# GrainDryer.net
KiCad netlist of a schematic drawn in Altium Designer
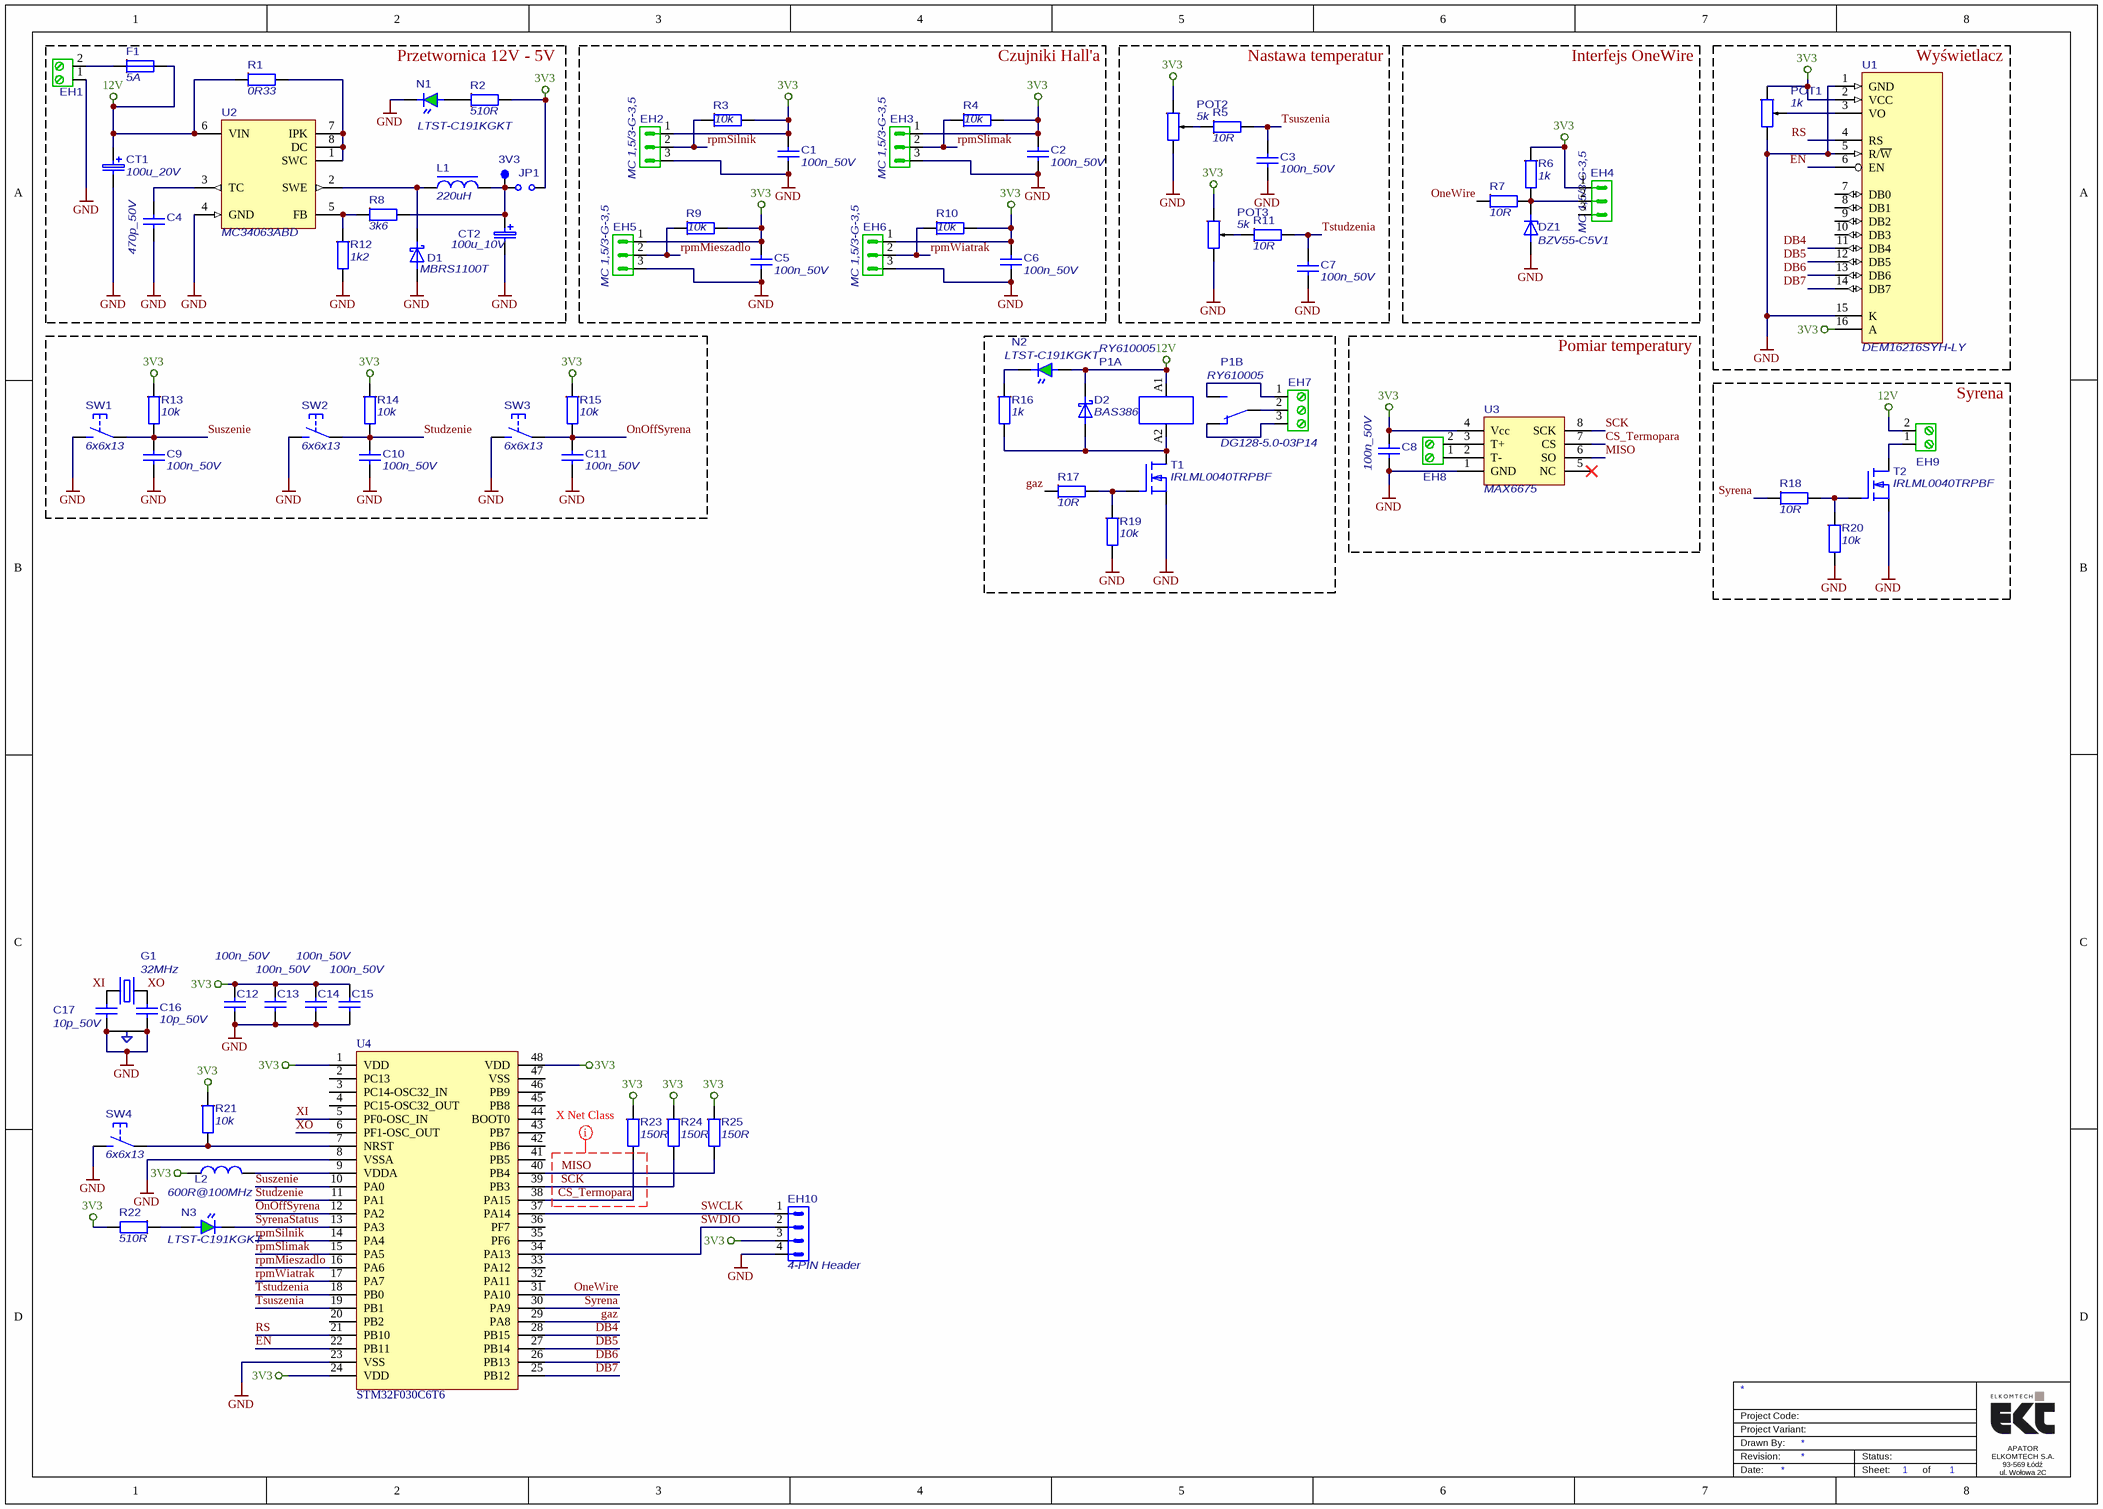
[diagram p0: GrainDryer.SchDoc]

(export (version "E")
  (design (tool "Eeschema 10.0.6"))
  (components
    (comp (ref "3V3")
      (value "TP_THT")
      (footprint "TP3")
      (description "Test Point, THT")
      (libsource (lib "manufacturing") (part "TP THT Dia{colon} 0,7mm"))
    )
    (comp (ref "C1")
      (value "100n_50V")
      (footprint "0603C")
      (description "Capacitor")
      (fields (field (name "TOLERANCE") "10") (field (name "MANUFACTURER") "MULTICOMP"))
      (libsource (lib "capacitor_smd") (part "100n 10% 50V 0603 [Metric{colon} 1608] X7R"))
    )
    (comp (ref "C2")
      (value "100n_50V")
      (footprint "0603C")
      (description "Capacitor")
      (fields (field (name "TOLERANCE") "10") (field (name "MANUFACTURER") "MULTICOMP"))
      (libsource (lib "capacitor_smd") (part "100n 10% 50V 0603 [Metric{colon} 1608] X7R"))
    )
    (comp (ref "C3")
      (value "100n_50V")
      (footprint "0603C")
      (description "Capacitor")
      (fields (field (name "TOLERANCE") "10") (field (name "MANUFACTURER") "MULTICOMP"))
      (libsource (lib "capacitor_smd") (part "100n 10% 50V 0603 [Metric{colon} 1608] X7R"))
    )
    (comp (ref "C4")
      (value "470p_50V")
      (footprint "1206C")
      (description "Capacitor")
      (fields (field (name "TOLERANCE") "5") (field (name "MANUFACTURER") "KEMET"))
      (libsource (lib "capacitor_smd") (part "470p 5% 50V 1206 [Metric{colon} 3216]"))
    )
    (comp (ref "C5")
      (value "100n_50V")
      (footprint "0603C")
      (description "Capacitor")
      (fields (field (name "TOLERANCE") "10") (field (name "MANUFACTURER") "MULTICOMP"))
      (libsource (lib "capacitor_smd") (part "100n 10% 50V 0603 [Metric{colon} 1608] X7R"))
    )
    (comp (ref "C6")
      (value "100n_50V")
      (footprint "0603C")
      (description "Capacitor")
      (fields (field (name "TOLERANCE") "10") (field (name "MANUFACTURER") "MULTICOMP"))
      (libsource (lib "capacitor_smd") (part "100n 10% 50V 0603 [Metric{colon} 1608] X7R"))
    )
    (comp (ref "C7")
      (value "100n_50V")
      (footprint "0603C")
      (description "Capacitor")
      (fields (field (name "TOLERANCE") "10") (field (name "MANUFACTURER") "MULTICOMP"))
      (libsource (lib "capacitor_smd") (part "100n 10% 50V 0603 [Metric{colon} 1608] X7R"))
    )
    (comp (ref "C8")
      (value "100n_50V")
      (footprint "0603C")
      (description "Capacitor")
      (fields (field (name "TOLERANCE") "10") (field (name "MANUFACTURER") "MULTICOMP"))
      (libsource (lib "capacitor_smd") (part "100n 10% 50V 0603 [Metric{colon} 1608] X7R"))
    )
    (comp (ref "C9")
      (value "100n_50V")
      (footprint "0603C")
      (description "Capacitor")
      (fields (field (name "TOLERANCE") "10") (field (name "MANUFACTURER") "MULTICOMP"))
      (libsource (lib "capacitor_smd") (part "100n 10% 50V 0603 [Metric{colon} 1608] X7R"))
    )
    (comp (ref "C10")
      (value "100n_50V")
      (footprint "0603C")
      (description "Capacitor")
      (fields (field (name "TOLERANCE") "10") (field (name "MANUFACTURER") "MULTICOMP"))
      (libsource (lib "capacitor_smd") (part "100n 10% 50V 0603 [Metric{colon} 1608] X7R"))
    )
    (comp (ref "C11")
      (value "100n_50V")
      (footprint "0603C")
      (description "Capacitor")
      (fields (field (name "TOLERANCE") "10") (field (name "MANUFACTURER") "MULTICOMP"))
      (libsource (lib "capacitor_smd") (part "100n 10% 50V 0603 [Metric{colon} 1608] X7R"))
    )
    (comp (ref "C12")
      (value "100n_50V")
      (footprint "0603C")
      (description "Capacitor")
      (fields (field (name "TOLERANCE") "10") (field (name "MANUFACTURER") "MULTICOMP"))
      (libsource (lib "capacitor_smd") (part "100n 10% 50V 0603 [Metric{colon} 1608] X7R"))
    )
    (comp (ref "C13")
      (value "100n_50V")
      (footprint "0603C")
      (description "Capacitor")
      (fields (field (name "TOLERANCE") "10") (field (name "MANUFACTURER") "MULTICOMP"))
      (libsource (lib "capacitor_smd") (part "100n 10% 50V 0603 [Metric{colon} 1608] X7R"))
    )
    (comp (ref "C14")
      (value "100n_50V")
      (footprint "0603C")
      (description "Capacitor")
      (fields (field (name "TOLERANCE") "10") (field (name "MANUFACTURER") "MULTICOMP"))
      (libsource (lib "capacitor_smd") (part "100n 10% 50V 0603 [Metric{colon} 1608] X7R"))
    )
    (comp (ref "C15")
      (value "100n_50V")
      (footprint "0603C")
      (description "Capacitor")
      (fields (field (name "TOLERANCE") "10") (field (name "MANUFACTURER") "MULTICOMP"))
      (libsource (lib "capacitor_smd") (part "100n 10% 50V 0603 [Metric{colon} 1608] X7R"))
    )
    (comp (ref "C16")
      (value "10p_50V")
      (footprint "0603H")
      (description "Capacitor")
      (fields (field (name "TOLERANCE") "5") (field (name "MANUFACTURER") "KEMET"))
      (libsource (lib "capacitor_smd") (part "10p 5% 50V 0603 [Metric{colon} 1608] C0G"))
    )
    (comp (ref "C17")
      (value "10p_50V")
      (footprint "0603H")
      (description "Capacitor")
      (fields (field (name "TOLERANCE") "5") (field (name "MANUFACTURER") "KEMET"))
      (libsource (lib "capacitor_smd") (part "10p 5% 50V 0603 [Metric{colon} 1608] C0G"))
    )
    (comp (ref "CT1")
      (value "100u_20V")
      (footprint "7243")
      (description "Tantalum Capacitor")
      (fields
        (field (name "MANUFACTURER") "AVX")
        (field (name "MANUFACTURER PART NUMBER") "TPSD107K020R0085")
      )
      (libsource (lib "capacitor_polarized_smd") (part "100u 10% 20V 2917 [Metric{colon} 7343] 0R085"))
    )
    (comp (ref "CT2")
      (value "100u_10V")
      (footprint "7243")
      (description "Tantalum Capacitor")
      (fields
        (field (name "MANUFACTURER") "AVX")
        (field (name "MANUFACTURER PART NUMBER") "TPSD107K010R0065")
      )
      (libsource (lib "capacitor_polarized_smd") (part "100u 10% 10V 2917 [Metric{colon} 7343] 0R065"))
    )
    (comp (ref "D1")
      (value "MBRS1100T")
      (footprint "CASE403A-03")
      (description "Schottky Diodes & Rectifiers")
      (fields
        (field (name "MANUFACTURER") "ON SEMICONDUCTOR")
        (field (name "MANUFACTURER PART NUMBER") "MBRS1100T3G")
      )
      (libsource (lib "diode_smd") (part "MBRS1100T3G 100V 1A SMB"))
    )
    (comp (ref "D2")
      (value "BAS386")
      (footprint "MICROMELF")
      (description "Schottky Diode")
      (fields (field (name "MANUFACTURER") "VISHAY") (field (name "MANUFACTURER PART NUMBER") "BAS386-TR"))
      (libsource (lib "diode_smd") (part "BAS386-TR 50V 0,1A Micro MELF"))
    )
    (comp (ref "DZ1")
      (value "BZV55-C5V1")
      (footprint "SOD80D")
      (description "Zener Diodes")
      (fields (field (name "MANUFACTURER") "NXP") (field (name "POWER") "0,5"))
      (libsource (lib "diode_zener_smd") (part "BZV55-C5V1 5,1V 2uA 500mW SOD-80"))
    )
    (comp (ref "EH1")
      (value "MKDSN 1,5/2-5,08")
      (footprint "2xMKDSN1.5")
      (description "Term. block 13,5A 250V")
      (fields
        (field (name "MANUFACTURER") "PHOENIX CONTACT")
        (field (name "MANUFACTURER PART NUMBER") "1729128")
      )
      (libsource (lib "phoenix_contact") (part "MKDSN 1,5/2-5,08 1729128"))
    )
    (comp (ref "EH2")
      (value "MC 1,5/3-G-3,5")
      (footprint "MC 1,5/3-G-3,5")
      (description "Header 8A 250V")
      (fields
        (field (name "MANUFACTURER") "PHOENIX CONTACT")
        (field (name "MANUFACTURER PART NUMBER") "1844223")
      )
      (libsource (lib "phoenix_contact") (part "MC 1,5/3-G-3,5 1844223"))
    )
    (comp (ref "EH3")
      (value "MC 1,5/3-G-3,5")
      (footprint "MC 1,5/3-G-3,5")
      (description "Header 8A 250V")
      (fields
        (field (name "MANUFACTURER") "PHOENIX CONTACT")
        (field (name "MANUFACTURER PART NUMBER") "1844223")
      )
      (libsource (lib "phoenix_contact") (part "MC 1,5/3-G-3,5 1844223"))
    )
    (comp (ref "EH4")
      (value "MC 1,5/3-G-3,5")
      (footprint "MC 1,5/3-G-3,5")
      (description "Header 8A 250V")
      (fields
        (field (name "MANUFACTURER") "PHOENIX CONTACT")
        (field (name "MANUFACTURER PART NUMBER") "1844223")
      )
      (libsource (lib "") (part "MC 1,5/3-G-3,5 1844223_1"))
    )
    (comp (ref "EH5")
      (value "MC 1,5/3-G-3,5")
      (footprint "MC 1,5/3-G-3,5")
      (description "Header 8A 250V")
      (fields
        (field (name "MANUFACTURER") "PHOENIX CONTACT")
        (field (name "MANUFACTURER PART NUMBER") "1844223")
      )
      (libsource (lib "phoenix_contact") (part "MC 1,5/3-G-3,5 1844223"))
    )
    (comp (ref "EH6")
      (value "MC 1,5/3-G-3,5")
      (footprint "MC 1,5/3-G-3,5")
      (description "Header 8A 250V")
      (fields
        (field (name "MANUFACTURER") "PHOENIX CONTACT")
        (field (name "MANUFACTURER PART NUMBER") "1844223")
      )
      (libsource (lib "phoenix_contact") (part "MC 1,5/3-G-3,5 1844223"))
    )
    (comp (ref "EH7")
      (value "DG128-5.0-03P14")
      (footprint "DG128-5.0-03P14")
      (description "Term. block 5mm")
      (fields
        (field (name "MANUFACTURER") "DEGSON ELECTRONICS")
        (field (name "MANUFACTURER PART NUMBER") "DG128-5.0-03P-14-00A(H)")
      )
      (libsource (lib "connector_pcb") (part "DG128-5.0-03P14"))
    )
    (comp (ref "EH8")
      (value "MKDSN 1,5/2-5,08")
      (footprint "2xMKDSN1.5")
      (description "Term. block 13,5A 250V")
      (fields
        (field (name "MANUFACTURER") "PHOENIX CONTACT")
        (field (name "MANUFACTURER PART NUMBER") "1729128")
      )
      (libsource (lib "phoenix_contact") (part "MKDSN 1,5/2-5,08 1729128"))
    )
    (comp (ref "EH9")
      (value "MKDSN 1,5/2-5,08")
      (footprint "2xMKDSN1.5")
      (description "Term. block 13,5A 250V")
      (fields
        (field (name "MANUFACTURER") "PHOENIX CONTACT")
        (field (name "MANUFACTURER PART NUMBER") "1729128")
      )
      (libsource (lib "") (part "MKDSN 1,5/2-5,08 1729128_1"))
    )
    (comp (ref "EH10")
      (value "4-PIN Header")
      (footprint "SIP4")
      (description "1x4, Male, Pitch 2,54mm")
      (fields
        (field (name "MANUFACTURER") "CONNFLY")
        (field (name "MANUFACTURER PART NUMBER") "DS1021-1*4SF1-1")
      )
      (libsource (lib "connector_pcb") (part "4-PIN Header 2,54 DS1021-1*4SF1-1"))
    )
    (comp (ref "F1")
      (value "5A")
      (footprint "20x5mm fuse holder")
      (description "Fuse")
      (fields (field (name "MANUFACTURER") "multicom") (field (name "MANUFACTURER PART NUMBER") "MC000827"))
      (libsource (lib "protection") (part "5A fuse 20x5mm"))
    )
    (comp (ref "G1")
      (value "32MHz")
      (footprint "XTAL2520")
      (description "25MHz; ±30ppm; 20pF; SMD; 2,6x2,1x0,65mm")
      (fields (field (name "MANUFACTURER") "YIC") (field (name "MANUFACTURER PART NUMBER") "32.00M-SMDXT224"))
      (libsource (lib "crystal_oscillator") (part "32.00M-SMDXT224 25MHz 30ppm -V 2,6x2,1"))
    )
    (comp (ref "JP1")
      (value "JP_2H_NO")
      (footprint "TIN2")
      (description "Jumper 2-contact, normally open")
      (libsource (lib "jumper") (part "JP 2H NO"))
    )
    (comp (ref "L1")
      (value "220uH")
      (footprint "SRR0604")
      (description "Power shielded 1R7")
      (fields
        (field (name "MANUFACTURER") "BOURNS")
        (field (name "MANUFACTURER PART NUMBER") "SRR0604-221KL")
      )
      (libsource (lib "inductor_smd") (part "220uH 0,25A 6,5x6,5x4,8"))
    )
    (comp (ref "L2")
      (value "600R@100MHz")
      (footprint "1206L")
      (description "EMI")
      (fields
        (field (name "MANUFACTURER") "MURATA")
        (field (name "MANUFACTURER PART NUMBER") "BLM31PG601SN1")
      )
      (libsource (lib "inductor_smd") (part "600R@100MHz 1,5A 1206"))
    )
    (comp (ref "N1")
      (value "LTST-C191KGKT")
      (footprint "LED0603GREEN")
      (description "LED SMD 12mcd")
      (fields (field (name "MANUFACTURER") "LITE-ON"))
      (libsource (lib "diode_led_smd") (part "LTST-C191KGKT Green 0603 [Metric{colon} 1608]"))
    )
    (comp (ref "N2")
      (value "LTST-C191KGKT")
      (footprint "LED0603GREEN")
      (description "LED SMD 12mcd")
      (fields (field (name "MANUFACTURER") "LITE-ON"))
      (libsource (lib "diode_led_smd") (part "LTST-C191KGKT Green 0603 [Metric{colon} 1608]"))
    )
    (comp (ref "N3")
      (value "LTST-C191KGKT")
      (footprint "LED0603GREEN")
      (description "LED SMD 12mcd")
      (fields (field (name "MANUFACTURER") "LITE-ON"))
      (libsource (lib "diode_led_smd") (part "LTST-C191KGKT Green 0603 [Metric{colon} 1608]"))
    )
    (comp (ref "P1")
      (value "RY610005")
      (footprint "RY6100XX")
      (description "General Purpose Relays SPDT 8 A 5VDC")
      (fields (field (name "MANUFACTURER") "SCHRACK"))
      (libsource (lib "") (part "RY610005_1"))
    )
    (comp (ref "POT1")
      (value "1k")
      (footprint "3312J")
      (description "Potentiometer")
      (fields (field (name "MANUFACTURER") "BOURNS") (field (name "MANUFACTURER PART NUMBER") "3312J-1-102E"))
      (libsource (lib "potentiometers") (part "1k 20% 0,1W SMD"))
    )
    (comp (ref "POT2")
      (value "5k")
      (footprint "3d_pot:RK09 vertical")
      (description "Potentiometer")
      (fields
        (field (name "MANUFACTURER") "SR PASSIVES")
        (field (name "MANUFACTURER PART NUMBER") "R9011-1-5K")
      )
      (libsource (lib "potentiometers") (part "5k 20% 1/8W THT RK09"))
    )
    (comp (ref "POT3")
      (value "5k")
      (footprint "3d_pot:RK09 vertical")
      (description "Potentiometer")
      (fields
        (field (name "MANUFACTURER") "SR PASSIVES")
        (field (name "MANUFACTURER PART NUMBER") "R9011-1-5K")
      )
      (libsource (lib "potentiometers") (part "5k 20% 1/8W THT RK09"))
    )
    (comp (ref "R1")
      (value "0R33")
      (footprint "2512R")
      (description "Resistor")
      (fields
        (field (name "MANUFACTURER") "YAGEO")
        (field (name "MANUFACTURER PART NUMBER") "RL2512JK-070R02L")
      )
      (libsource (lib "resistor_smd") (part "0R33 5% 1W 2512 [Metric{colon} 6432]"))
    )
    (comp (ref "R2")
      (value "510R")
      (footprint "0603R")
      (description "Resistor")
      (fields
        (field (name "MANUFACTURER") "YAGEO")
        (field (name "MANUFACTURER PART NUMBER") "RC0603JR-07510RL")
      )
      (libsource (lib "") (part "510R 5% 0,1W 0603 [Metric{colon} 1608]_1"))
    )
    (comp (ref "R3")
      (value "10k")
      (footprint "0603R")
      (description "Resistor")
      (fields
        (field (name "MANUFACTURER") "YAGEO")
        (field (name "MANUFACTURER PART NUMBER") "RC0603JR-0710KL")
      )
      (libsource (lib "resistor_smd") (part "10k 5% 0,1W 0603 [Metric{colon} 1608]"))
    )
    (comp (ref "R4")
      (value "10k")
      (footprint "0603R")
      (description "Resistor")
      (fields
        (field (name "MANUFACTURER") "YAGEO")
        (field (name "MANUFACTURER PART NUMBER") "RC0603JR-0710KL")
      )
      (libsource (lib "resistor_smd") (part "10k 5% 0,1W 0603 [Metric{colon} 1608]"))
    )
    (comp (ref "R5")
      (value "10R")
      (footprint "0603R")
      (description "Resistor")
      (fields
        (field (name "MANUFACTURER") "PANASONIC")
        (field (name "MANUFACTURER PART NUMBER") "ERJ3EKF10R0V")
      )
      (libsource (lib "resistor_smd") (part "10R 1% 0,1W 0603 [Metric{colon} 1608]"))
    )
    (comp (ref "R6")
      (value "1k")
      (footprint "0603R")
      (description "Resistor")
      (fields
        (field (name "MANUFACTURER") "YAGEO")
        (field (name "MANUFACTURER PART NUMBER") "RC0603JR-071KL")
      )
      (libsource (lib "") (part "1k 5% 0,1W 0603 [Metric{colon} 1608]_1"))
    )
    (comp (ref "R7")
      (value "10R")
      (footprint "0603R")
      (description "Resistor")
      (fields
        (field (name "MANUFACTURER") "PANASONIC")
        (field (name "MANUFACTURER PART NUMBER") "ERJ3EKF10R0V")
      )
      (libsource (lib "resistor_smd") (part "10R 1% 0,1W 0603 [Metric{colon} 1608]"))
    )
    (comp (ref "R8")
      (value "3k6")
      (footprint "1206R")
      (description "Resistor")
      (fields
        (field (name "MANUFACTURER") "PANASONIC")
        (field (name "MANUFACTURER PART NUMBER") "ERJ8ENF3601V")
      )
      (libsource (lib "resistor_smd") (part "3k6 1% 0,25W 1206 [Metric{colon} 3216]"))
    )
    (comp (ref "R9")
      (value "10k")
      (footprint "0603R")
      (description "Resistor")
      (fields
        (field (name "MANUFACTURER") "YAGEO")
        (field (name "MANUFACTURER PART NUMBER") "RC0603JR-0710KL")
      )
      (libsource (lib "resistor_smd") (part "10k 5% 0,1W 0603 [Metric{colon} 1608]"))
    )
    (comp (ref "R10")
      (value "10k")
      (footprint "0603R")
      (description "Resistor")
      (fields
        (field (name "MANUFACTURER") "YAGEO")
        (field (name "MANUFACTURER PART NUMBER") "RC0603JR-0710KL")
      )
      (libsource (lib "resistor_smd") (part "10k 5% 0,1W 0603 [Metric{colon} 1608]"))
    )
    (comp (ref "R11")
      (value "10R")
      (footprint "0603R")
      (description "Resistor")
      (fields
        (field (name "MANUFACTURER") "PANASONIC")
        (field (name "MANUFACTURER PART NUMBER") "ERJ3EKF10R0V")
      )
      (libsource (lib "resistor_smd") (part "10R 1% 0,1W 0603 [Metric{colon} 1608]"))
    )
    (comp (ref "R12")
      (value "1k2")
      (footprint "1206R")
      (description "Resistor")
      (fields
        (field (name "MANUFACTURER") "ROYAL OHM")
        (field (name "MANUFACTURER PART NUMBER") "1206S4F0122T5E")
      )
      (libsource (lib "resistor_smd") (part "1k2 1% 0,25W 1206 [Metric{colon} 3216]"))
    )
    (comp (ref "R13")
      (value "10k")
      (footprint "0603R")
      (description "Resistor")
      (fields
        (field (name "MANUFACTURER") "YAGEO")
        (field (name "MANUFACTURER PART NUMBER") "RC0603JR-0710KL")
      )
      (libsource (lib "resistor_smd") (part "10k 5% 0,1W 0603 [Metric{colon} 1608]"))
    )
    (comp (ref "R14")
      (value "10k")
      (footprint "0603R")
      (description "Resistor")
      (fields
        (field (name "MANUFACTURER") "YAGEO")
        (field (name "MANUFACTURER PART NUMBER") "RC0603JR-0710KL")
      )
      (libsource (lib "resistor_smd") (part "10k 5% 0,1W 0603 [Metric{colon} 1608]"))
    )
    (comp (ref "R15")
      (value "10k")
      (footprint "0603R")
      (description "Resistor")
      (fields
        (field (name "MANUFACTURER") "YAGEO")
        (field (name "MANUFACTURER PART NUMBER") "RC0603JR-0710KL")
      )
      (libsource (lib "resistor_smd") (part "10k 5% 0,1W 0603 [Metric{colon} 1608]"))
    )
    (comp (ref "R16")
      (value "1k")
      (footprint "0603R")
      (description "Resistor")
      (fields
        (field (name "MANUFACTURER") "YAGEO")
        (field (name "MANUFACTURER PART NUMBER") "RC0603JR-071KL")
      )
      (libsource (lib "resistor_smd") (part "1k 5% 0,1W 0603 [Metric{colon} 1608]"))
    )
    (comp (ref "R17")
      (value "10R")
      (footprint "0603R")
      (description "Resistor")
      (fields
        (field (name "MANUFACTURER") "PANASONIC")
        (field (name "MANUFACTURER PART NUMBER") "ERJ3EKF10R0V")
      )
      (libsource (lib "resistor_smd") (part "10R 1% 0,1W 0603 [Metric{colon} 1608]"))
    )
    (comp (ref "R18")
      (value "10R")
      (footprint "0603R")
      (description "Resistor")
      (fields
        (field (name "MANUFACTURER") "PANASONIC")
        (field (name "MANUFACTURER PART NUMBER") "ERJ3EKF10R0V")
      )
      (libsource (lib "resistor_smd") (part "10R 1% 0,1W 0603 [Metric{colon} 1608]"))
    )
    (comp (ref "R19")
      (value "10k")
      (footprint "0603R")
      (description "Resistor")
      (fields
        (field (name "MANUFACTURER") "YAGEO")
        (field (name "MANUFACTURER PART NUMBER") "RC0603JR-0710KL")
      )
      (libsource (lib "resistor_smd") (part "10k 5% 0,1W 0603 [Metric{colon} 1608]"))
    )
    (comp (ref "R20")
      (value "10k")
      (footprint "0603R")
      (description "Resistor")
      (fields
        (field (name "MANUFACTURER") "YAGEO")
        (field (name "MANUFACTURER PART NUMBER") "RC0603JR-0710KL")
      )
      (libsource (lib "resistor_smd") (part "10k 5% 0,1W 0603 [Metric{colon} 1608]"))
    )
    (comp (ref "R21")
      (value "10k")
      (footprint "0603R")
      (description "Resistor")
      (fields
        (field (name "MANUFACTURER") "YAGEO")
        (field (name "MANUFACTURER PART NUMBER") "RC0603JR-0710KL")
      )
      (libsource (lib "resistor_smd") (part "10k 5% 0,1W 0603 [Metric{colon} 1608]"))
    )
    (comp (ref "R22")
      (value "510R")
      (footprint "0603R")
      (description "Resistor")
      (fields
        (field (name "MANUFACTURER") "YAGEO")
        (field (name "MANUFACTURER PART NUMBER") "RC0603JR-07510RL")
      )
      (libsource (lib "resistor_smd") (part "510R 5% 0,1W 0603 [Metric{colon} 1608]"))
    )
    (comp (ref "R23")
      (value "150R")
      (footprint "0603R")
      (description "Resistor")
      (fields
        (field (name "MANUFACTURER") "YAGEO")
        (field (name "MANUFACTURER PART NUMBER") "RC0603JR-07150RL")
      )
      (libsource (lib "resistor_smd") (part "150R 5% 0,1W 0603 [Metric{colon} 1608]"))
    )
    (comp (ref "R24")
      (value "150R")
      (footprint "0603R")
      (description "Resistor")
      (fields
        (field (name "MANUFACTURER") "YAGEO")
        (field (name "MANUFACTURER PART NUMBER") "RC0603JR-07150RL")
      )
      (libsource (lib "resistor_smd") (part "150R 5% 0,1W 0603 [Metric{colon} 1608]"))
    )
    (comp (ref "R25")
      (value "150R")
      (footprint "0603R")
      (description "Resistor")
      (fields
        (field (name "MANUFACTURER") "YAGEO")
        (field (name "MANUFACTURER PART NUMBER") "RC0603JR-07150RL")
      )
      (libsource (lib "resistor_smd") (part "150R 5% 0,1W 0603 [Metric{colon} 1608]"))
    )
    (comp (ref "SW1")
      (value "6x6x13")
      (footprint "SW6x6x13")
      (description "SW 6x6x13")
      (fields (field (name "MANUFACTURER") "NINIGI") (field (name "MANUFACTURER PART NUMBER") "TACT-613N-F"))
      (libsource (lib "switch") (part "SW6x6x13"))
    )
    (comp (ref "SW2")
      (value "6x6x13")
      (footprint "SW6x6x13")
      (description "SW 6x6x13")
      (fields (field (name "MANUFACTURER") "NINIGI") (field (name "MANUFACTURER PART NUMBER") "TACT-613N-F"))
      (libsource (lib "switch") (part "SW6x6x13"))
    )
    (comp (ref "SW3")
      (value "6x6x13")
      (footprint "SW6x6x13")
      (description "SW 6x6x13")
      (fields (field (name "MANUFACTURER") "NINIGI") (field (name "MANUFACTURER PART NUMBER") "TACT-613N-F"))
      (libsource (lib "switch") (part "SW6x6x13"))
    )
    (comp (ref "SW4")
      (value "6x6x13")
      (footprint "SW6x6x13")
      (description "SW 6x6x13")
      (fields (field (name "MANUFACTURER") "NINIGI") (field (name "MANUFACTURER PART NUMBER") "TACT-613N-F"))
      (libsource (lib "switch") (part "SW6x6x13"))
    )
    (comp (ref "T1")
      (value "IRLML0040TRPBF")
      (footprint "SOT23")
      (description "N-MOS 40V 3.6A 56mOhm 2.6nC Qg")
      (fields (field (name "MANUFACTURER") "INTERNATIONAL RECTIFIER"))
      (libsource (lib "transistor") (part "IRLML0040TRPBF N 3,6A 40V SOT-23"))
    )
    (comp (ref "T2")
      (value "IRLML0040TRPBF")
      (footprint "SOT23")
      (description "N-MOS 40V 3.6A 56mOhm 2.6nC Qg")
      (fields (field (name "MANUFACTURER") "INTERNATIONAL RECTIFIER"))
      (libsource (lib "transistor") (part "IRLML0040TRPBF N 3,6A 40V SOT-23"))
    )
    (comp (ref "U1")
      (value "DEM16216SYH-LY")
      (footprint "LCD2004")
      (description "LCD 4x20 93 x 55 mm 5V BL")
      (fields (field (name "MANUFACTURER") "DISPLAY ELEKTRONIK"))
      (libsource (lib "display") (part "LCD2004"))
    )
    (comp (ref "U2")
      (value "MC34063ABD")
      (footprint "so8")
      (description "DC-DC converter")
      (fields (field (name "MANUFACTURER") "STMICROELECTRONICS"))
      (libsource (lib "power") (part "MC34063A"))
    )
    (comp (ref "U3")
      (value "MAX6675")
      (footprint "SO8")
      (description "Cold-Junction-Compensated K-Thermocouple-to-Digital Converter")
      (fields (field (name "MANUFACTURER") "Maxim Integrated"))
      (libsource (lib "analog") (part "MAX6675"))
    )
    (comp (ref "U4")
      (value "STM32F030C6T6")
      (footprint "LQFP48(0.5)")
      (description "Cortex M0, Flash 32k RAM 8k")
      (fields (field (name "MANUFACTURER") "STMICROELECTRONICS"))
      (libsource (lib "processor") (part "STM32F030C6T6"))
    )
  )
  (nets
    (net (code "1") (name "/CS_Termopara") (class "Default")
      (node (ref "R23") (pin "2") (pinfunction "2_2") (pintype "passive"))
      (node (ref "U3") (pin "7") (pinfunction "CS_7") (pintype "passive"))
      (node (ref "U4") (pin "38") (pinfunction "PA15_38") (pintype "passive"))
    )
    (net (code "2") (name "/DB4") (class "Default")
      (node (ref "U1") (pin "11") (pinfunction "DB4_11") (pintype "bidirectional"))
      (node (ref "U4") (pin "28") (pinfunction "PB15_28") (pintype "passive"))
    )
    (net (code "3") (name "/DB5") (class "Default")
      (node (ref "U1") (pin "12") (pinfunction "DB5_12") (pintype "bidirectional"))
      (node (ref "U4") (pin "27") (pinfunction "PB14_27") (pintype "passive"))
    )
    (net (code "4") (name "/DB6") (class "Default")
      (node (ref "U1") (pin "13") (pinfunction "DB6_13") (pintype "bidirectional"))
      (node (ref "U4") (pin "26") (pinfunction "PB13_26") (pintype "passive"))
    )
    (net (code "5") (name "/DB7") (class "Default")
      (node (ref "U1") (pin "14") (pinfunction "DB7_14") (pintype "bidirectional"))
      (node (ref "U4") (pin "25") (pinfunction "PB12_25") (pintype "passive"))
    )
    (net (code "6") (name "/EN") (class "Default")
      (node (ref "U1") (pin "6") (pinfunction "EN_6") (pintype "passive"))
      (node (ref "U4") (pin "22") (pinfunction "PB11_22") (pintype "passive"))
    )
    (net (code "7") (name "/MISO") (class "Default")
      (node (ref "R25") (pin "2") (pinfunction "2_2") (pintype "passive"))
      (node (ref "U3") (pin "6") (pinfunction "SO_6") (pintype "passive"))
      (node (ref "U4") (pin "40") (pinfunction "PB4_40") (pintype "passive"))
    )
    (net (code "8") (name "/OnOffSyrena") (class "Default")
      (node (ref "C11") (pin "1") (pinfunction "1_1") (pintype "passive"))
      (node (ref "R15") (pin "2") (pinfunction "2_2") (pintype "passive"))
      (node (ref "SW3") (pin "2") (pinfunction "2_2") (pintype "passive"))
      (node (ref "U4") (pin "12") (pinfunction "PA2_12") (pintype "passive"))
    )
    (net (code "9") (name "/OneWire") (class "Default")
      (node (ref "R7") (pin "1") (pinfunction "1_1") (pintype "passive"))
      (node (ref "U4") (pin "31") (pinfunction "PA10_31") (pintype "passive"))
    )
    (net (code "10") (name "/RS") (class "Default")
      (node (ref "U1") (pin "4") (pinfunction "RS_4") (pintype "passive"))
      (node (ref "U4") (pin "21") (pinfunction "PB10_21") (pintype "passive"))
    )
    (net (code "11") (name "/SCK") (class "Default")
      (node (ref "R24") (pin "2") (pinfunction "2_2") (pintype "passive"))
      (node (ref "U3") (pin "8") (pinfunction "SCK_8") (pintype "passive"))
      (node (ref "U4") (pin "39") (pinfunction "PB3_39") (pintype "passive"))
    )
    (net (code "12") (name "/SWCLK") (class "Default")
      (node (ref "EH10") (pin "1") (pinfunction "1_1") (pintype "passive"))
      (node (ref "U4") (pin "37") (pinfunction "PA14_37") (pintype "passive"))
    )
    (net (code "13") (name "/SWDIO") (class "Default")
      (node (ref "EH10") (pin "2") (pinfunction "2_2") (pintype "passive"))
      (node (ref "U4") (pin "34") (pinfunction "PA13_34") (pintype "passive"))
    )
    (net (code "14") (name "/Studzenie") (class "Default")
      (node (ref "C10") (pin "1") (pinfunction "1_1") (pintype "passive"))
      (node (ref "R14") (pin "2") (pinfunction "2_2") (pintype "passive"))
      (node (ref "SW2") (pin "2") (pinfunction "2_2") (pintype "passive"))
      (node (ref "U4") (pin "11") (pinfunction "PA1_11") (pintype "passive"))
    )
    (net (code "15") (name "/Suszenie") (class "Default")
      (node (ref "C9") (pin "1") (pinfunction "1_1") (pintype "passive"))
      (node (ref "R13") (pin "2") (pinfunction "2_2") (pintype "passive"))
      (node (ref "SW1") (pin "2") (pinfunction "2_2") (pintype "passive"))
      (node (ref "U4") (pin "10") (pinfunction "PA0_10") (pintype "passive"))
    )
    (net (code "16") (name "/Syrena") (class "Default")
      (node (ref "R18") (pin "1") (pinfunction "1_1") (pintype "passive"))
      (node (ref "U4") (pin "30") (pinfunction "PA9_30") (pintype "passive"))
    )
    (net (code "17") (name "/SyrenaStatus") (class "Default")
      (node (ref "N3") (pin "1") (pinfunction "K_1") (pintype "passive"))
      (node (ref "U4") (pin "13") (pinfunction "PA3_13") (pintype "passive"))
    )
    (net (code "18") (name "/Tstudzenia") (class "Default")
      (node (ref "C7") (pin "1") (pinfunction "1_1") (pintype "passive"))
      (node (ref "R11") (pin "2") (pinfunction "2_2") (pintype "passive"))
      (node (ref "U4") (pin "18") (pinfunction "PB0_18") (pintype "passive"))
    )
    (net (code "19") (name "/Tsuszenia") (class "Default")
      (node (ref "C3") (pin "1") (pinfunction "1_1") (pintype "passive"))
      (node (ref "R5") (pin "2") (pinfunction "2_2") (pintype "passive"))
      (node (ref "U4") (pin "19") (pinfunction "PB1_19") (pintype "passive"))
    )
    (net (code "20") (name "/XI") (class "Default")
      (node (ref "C17") (pin "1") (pinfunction "1_1") (pintype "passive"))
      (node (ref "G1") (pin "1") (pinfunction "1_1") (pintype "passive"))
      (node (ref "U4") (pin "5") (pinfunction "PF0-OSC_IN_5") (pintype "passive"))
    )
    (net (code "21") (name "/XO") (class "Default")
      (node (ref "C16") (pin "1") (pinfunction "1_1") (pintype "passive"))
      (node (ref "G1") (pin "3") (pinfunction "3_3") (pintype "passive"))
      (node (ref "U4") (pin "6") (pinfunction "PF1-OSC_OUT_6") (pintype "passive"))
    )
    (net (code "22") (name "/gaz") (class "Default")
      (node (ref "R17") (pin "1") (pinfunction "1_1") (pintype "passive"))
      (node (ref "U4") (pin "29") (pinfunction "PA8_29") (pintype "passive"))
    )
    (net (code "23") (name "/rpmMieszadlo") (class "Default")
      (node (ref "EH5") (pin "2") (pinfunction "2_2") (pintype "passive"))
      (node (ref "R9") (pin "1") (pinfunction "1_1") (pintype "passive"))
      (node (ref "U4") (pin "16") (pinfunction "PA6_16") (pintype "passive"))
    )
    (net (code "24") (name "/rpmSilnik") (class "Default")
      (node (ref "EH2") (pin "2") (pinfunction "2_2") (pintype "passive"))
      (node (ref "R3") (pin "1") (pinfunction "1_1") (pintype "passive"))
      (node (ref "U4") (pin "14") (pinfunction "PA4_14") (pintype "passive"))
    )
    (net (code "25") (name "/rpmSlimak") (class "Default")
      (node (ref "EH3") (pin "2") (pinfunction "2_2") (pintype "passive"))
      (node (ref "R4") (pin "1") (pinfunction "1_1") (pintype "passive"))
      (node (ref "U4") (pin "15") (pinfunction "PA5_15") (pintype "passive"))
    )
    (net (code "26") (name "/rpmWiatrak") (class "Default")
      (node (ref "EH6") (pin "2") (pinfunction "2_2") (pintype "passive"))
      (node (ref "R10") (pin "1") (pinfunction "1_1") (pintype "passive"))
      (node (ref "U4") (pin "17") (pinfunction "PA7_17") (pintype "passive"))
    )
    (net (code "27") (name "3V3") (class "Default")
      (node (ref "C1") (pin "1") (pinfunction "1_1") (pintype "passive"))
      (node (ref "C12") (pin "1") (pinfunction "1_1") (pintype "passive"))
      (node (ref "C13") (pin "1") (pinfunction "1_1") (pintype "passive"))
      (node (ref "C14") (pin "1") (pinfunction "1_1") (pintype "passive"))
      (node (ref "C15") (pin "1") (pinfunction "1_1") (pintype "passive"))
      (node (ref "C2") (pin "1") (pinfunction "1_1") (pintype "passive"))
      (node (ref "C5") (pin "1") (pinfunction "1_1") (pintype "passive"))
      (node (ref "C6") (pin "1") (pinfunction "1_1") (pintype "passive"))
      (node (ref "C8") (pin "1") (pinfunction "1_1") (pintype "passive"))
      (node (ref "EH10") (pin "3") (pinfunction "3_3") (pintype "passive"))
      (node (ref "EH2") (pin "1") (pinfunction "1_1") (pintype "passive"))
      (node (ref "EH3") (pin "1") (pinfunction "1_1") (pintype "passive"))
      (node (ref "EH4") (pin "1") (pinfunction "1_1") (pintype "passive"))
      (node (ref "EH5") (pin "1") (pinfunction "1_1") (pintype "passive"))
      (node (ref "EH6") (pin "1") (pinfunction "1_1") (pintype "passive"))
      (node (ref "JP1") (pin "2") (pinfunction "2_2") (pintype "passive"))
      (node (ref "L2") (pin "1") (pinfunction "1_1") (pintype "passive"))
      (node (ref "POT1") (pin "1") (pinfunction "1_1") (pintype "passive"))
      (node (ref "POT2") (pin "1") (pinfunction "1_1") (pintype "passive"))
      (node (ref "POT3") (pin "1") (pinfunction "1_1") (pintype "passive"))
      (node (ref "R10") (pin "2") (pinfunction "2_2") (pintype "passive"))
      (node (ref "R13") (pin "1") (pinfunction "1_1") (pintype "passive"))
      (node (ref "R14") (pin "1") (pinfunction "1_1") (pintype "passive"))
      (node (ref "R15") (pin "1") (pinfunction "1_1") (pintype "passive"))
      (node (ref "R2") (pin "2") (pinfunction "2_2") (pintype "passive"))
      (node (ref "R21") (pin "1") (pinfunction "1_1") (pintype "passive"))
      (node (ref "R22") (pin "2") (pinfunction "2_2") (pintype "passive"))
      (node (ref "R23") (pin "1") (pinfunction "1_1") (pintype "passive"))
      (node (ref "R24") (pin "1") (pinfunction "1_1") (pintype "passive"))
      (node (ref "R25") (pin "1") (pinfunction "1_1") (pintype "passive"))
      (node (ref "R3") (pin "2") (pinfunction "2_2") (pintype "passive"))
      (node (ref "R4") (pin "2") (pinfunction "2_2") (pintype "passive"))
      (node (ref "R6") (pin "1") (pinfunction "1_1") (pintype "passive"))
      (node (ref "R9") (pin "2") (pinfunction "2_2") (pintype "passive"))
      (node (ref "U1") (pin "16") (pinfunction "A_16") (pintype "power_in"))
      (node (ref "U1") (pin "2") (pinfunction "VCC_2") (pintype "input"))
      (node (ref "U3") (pin "4") (pinfunction "Vcc_4") (pintype "passive"))
      (node (ref "U4") (pin "1") (pinfunction "VDD_1") (pintype "passive"))
      (node (ref "U4") (pin "24") (pinfunction "VDD_24") (pintype "passive"))
      (node (ref "U4") (pin "48") (pinfunction "VDD_48") (pintype "passive"))
    )
    (net (code "28") (name "12V") (class "Default")
      (node (ref "CT1") (pin "1") (pinfunction "1_1") (pintype "passive"))
      (node (ref "D2") (pin "1") (pinfunction "K_1") (pintype "passive"))
      (node (ref "EH9") (pin "2") (pinfunction "2_2") (pintype "passive"))
      (node (ref "F1") (pin "2") (pinfunction "2_2") (pintype "passive"))
      (node (ref "N2") (pin "2") (pinfunction "A_2") (pintype "passive"))
      (node (ref "P1") (pin "A1") (pinfunction "A1_A1") (pintype "passive"))
      (node (ref "R1") (pin "1") (pinfunction "1_1") (pintype "passive"))
      (node (ref "U2") (pin "6") (pinfunction "VIN_6") (pintype "passive"))
    )
    (net (code "29") (name "GND") (class "Default")
      (node (ref "C1") (pin "2") (pinfunction "2_2") (pintype "passive"))
      (node (ref "C10") (pin "2") (pinfunction "2_2") (pintype "passive"))
      (node (ref "C11") (pin "2") (pinfunction "2_2") (pintype "passive"))
      (node (ref "C12") (pin "2") (pinfunction "2_2") (pintype "passive"))
      (node (ref "C13") (pin "2") (pinfunction "2_2") (pintype "passive"))
      (node (ref "C14") (pin "2") (pinfunction "2_2") (pintype "passive"))
      (node (ref "C15") (pin "2") (pinfunction "2_2") (pintype "passive"))
      (node (ref "C16") (pin "2") (pinfunction "2_2") (pintype "passive"))
      (node (ref "C17") (pin "2") (pinfunction "2_2") (pintype "passive"))
      (node (ref "C2") (pin "2") (pinfunction "2_2") (pintype "passive"))
      (node (ref "C3") (pin "2") (pinfunction "2_2") (pintype "passive"))
      (node (ref "C4") (pin "1") (pinfunction "1_1") (pintype "passive"))
      (node (ref "C5") (pin "2") (pinfunction "2_2") (pintype "passive"))
      (node (ref "C6") (pin "2") (pinfunction "2_2") (pintype "passive"))
      (node (ref "C7") (pin "2") (pinfunction "2_2") (pintype "passive"))
      (node (ref "C8") (pin "2") (pinfunction "2_2") (pintype "passive"))
      (node (ref "C9") (pin "2") (pinfunction "2_2") (pintype "passive"))
      (node (ref "CT1") (pin "2") (pinfunction "2_2") (pintype "passive"))
      (node (ref "CT2") (pin "2") (pinfunction "2_2") (pintype "passive"))
      (node (ref "D1") (pin "2") (pinfunction "A_2") (pintype "passive"))
      (node (ref "DZ1") (pin "2") (pinfunction "A_2") (pintype "passive"))
      (node (ref "EH1") (pin "1") (pinfunction "1_1") (pintype "passive"))
      (node (ref "EH10") (pin "4") (pinfunction "4_4") (pintype "passive"))
      (node (ref "EH2") (pin "3") (pinfunction "3_3") (pintype "passive"))
      (node (ref "EH3") (pin "3") (pinfunction "3_3") (pintype "passive"))
      (node (ref "EH5") (pin "3") (pinfunction "3_3") (pintype "passive"))
      (node (ref "EH6") (pin "3") (pinfunction "3_3") (pintype "passive"))
      (node (ref "G1") (pin "2") (pinfunction "GND_2") (pintype "power_in"))
      (node (ref "G1") (pin "4") (pinfunction "GND_4") (pintype "power_in"))
      (node (ref "N1") (pin "1") (pinfunction "K_1") (pintype "passive"))
      (node (ref "POT1") (pin "3") (pinfunction "3_3") (pintype "passive"))
      (node (ref "POT2") (pin "3") (pinfunction "3_3") (pintype "passive"))
      (node (ref "POT3") (pin "3") (pinfunction "3_3") (pintype "passive"))
      (node (ref "R12") (pin "2") (pinfunction "2_2") (pintype "passive"))
      (node (ref "R19") (pin "2") (pinfunction "2_2") (pintype "passive"))
      (node (ref "R20") (pin "2") (pinfunction "2_2") (pintype "passive"))
      (node (ref "SW1") (pin "1") (pinfunction "1_1") (pintype "passive"))
      (node (ref "SW2") (pin "1") (pinfunction "1_1") (pintype "passive"))
      (node (ref "SW3") (pin "1") (pinfunction "1_1") (pintype "passive"))
      (node (ref "SW4") (pin "1") (pinfunction "1_1") (pintype "passive"))
      (node (ref "T1") (pin "2") (pinfunction "S_2") (pintype "passive"))
      (node (ref "T2") (pin "2") (pinfunction "S_2") (pintype "passive"))
      (node (ref "U1") (pin "1") (pinfunction "GND_1") (pintype "input"))
      (node (ref "U1") (pin "15") (pinfunction "K_15") (pintype "power_in"))
      (node (ref "U1") (pin "5") (pinfunction "R/~{W}_5") (pintype "input"))
      (node (ref "U2") (pin "4") (pinfunction "GND_4") (pintype "input"))
      (node (ref "U3") (pin "1") (pinfunction "GND_1") (pintype "passive"))
      (node (ref "U4") (pin "23") (pinfunction "VSS_23") (pintype "passive"))
      (node (ref "U4") (pin "8") (pinfunction "VSSA_8") (pintype "passive"))
    )
    (net (code "30") (name "Net-(3V3-Pad1)") (class "Default")
      (node (ref "3V3") (pin "1") (pinfunction "1_1") (pintype "passive"))
      (node (ref "CT2") (pin "1") (pinfunction "1_1") (pintype "passive"))
      (node (ref "JP1") (pin "1") (pinfunction "1_1") (pintype "passive"))
      (node (ref "L1") (pin "1") (pinfunction "1_1") (pintype "passive"))
      (node (ref "R8") (pin "2") (pinfunction "2_2") (pintype "passive"))
    )
    (net (code "31") (name "Net-(D1-K)") (class "Default")
      (node (ref "D1") (pin "1") (pinfunction "K_1") (pintype "passive"))
      (node (ref "L1") (pin "2") (pinfunction "2_2") (pintype "passive"))
      (node (ref "U2") (pin "2") (pinfunction "SWE_2") (pintype "output"))
    )
    (net (code "32") (name "Net-(D2-A)") (class "Default")
      (node (ref "D2") (pin "2") (pinfunction "A_2") (pintype "passive"))
      (node (ref "P1") (pin "A2") (pinfunction "A2_A2") (pintype "passive"))
      (node (ref "R16") (pin "2") (pinfunction "2_2") (pintype "passive"))
      (node (ref "T1") (pin "3") (pinfunction "D_3") (pintype "passive"))
    )
    (net (code "33") (name "Net-(DZ1-K)") (class "Default")
      (node (ref "DZ1") (pin "1") (pinfunction "K_1") (pintype "passive"))
      (node (ref "EH4") (pin "2") (pinfunction "2_2") (pintype "passive"))
      (node (ref "R6") (pin "2") (pinfunction "2_2") (pintype "passive"))
      (node (ref "R7") (pin "2") (pinfunction "2_2") (pintype "passive"))
    )
    (net (code "34") (name "Net-(EH1-Pad2)") (class "Default")
      (node (ref "EH1") (pin "2") (pinfunction "2_2") (pintype "passive"))
      (node (ref "F1") (pin "1") (pinfunction "1_1") (pintype "passive"))
    )
    (net (code "35") (name "Net-(EH7-Pad1)") (class "Default")
      (node (ref "EH7") (pin "1") (pinfunction "1_1") (pintype "passive"))
      (node (ref "P1") (pin "14") (pinfunction "14_14") (pintype "passive"))
    )
    (net (code "36") (name "Net-(EH7-Pad2)") (class "Default")
      (node (ref "EH7") (pin "2") (pinfunction "2_2") (pintype "passive"))
      (node (ref "P1") (pin "11") (pinfunction "11_11") (pintype "passive"))
    )
    (net (code "37") (name "Net-(EH7-Pad3)") (class "Default")
      (node (ref "EH7") (pin "3") (pinfunction "3_3") (pintype "passive"))
      (node (ref "P1") (pin "12") (pinfunction "12_12") (pintype "passive"))
    )
    (net (code "38") (name "Net-(N1-A)") (class "Default")
      (node (ref "N1") (pin "2") (pinfunction "A_2") (pintype "passive"))
      (node (ref "R2") (pin "1") (pinfunction "1_1") (pintype "passive"))
    )
    (net (code "39") (name "Net-(N2-K)") (class "Default")
      (node (ref "N2") (pin "1") (pinfunction "K_1") (pintype "passive"))
      (node (ref "R16") (pin "1") (pinfunction "1_1") (pintype "passive"))
    )
    (net (code "40") (name "Net-(N3-A)") (class "Default")
      (node (ref "N3") (pin "2") (pinfunction "A_2") (pintype "passive"))
      (node (ref "R22") (pin "1") (pinfunction "1_1") (pintype "passive"))
    )
    (net (code "41") (name "Net-(POT2-Pad2)") (class "Default")
      (node (ref "POT2") (pin "2") (pinfunction "2_2") (pintype "passive"))
      (node (ref "R5") (pin "1") (pinfunction "1_1") (pintype "passive"))
    )
    (net (code "42") (name "Net-(POT3-Pad2)") (class "Default")
      (node (ref "POT3") (pin "2") (pinfunction "2_2") (pintype "passive"))
      (node (ref "R11") (pin "1") (pinfunction "1_1") (pintype "passive"))
    )
    (net (code "43") (name "Net-(T1-G)") (class "Default")
      (node (ref "R17") (pin "2") (pinfunction "2_2") (pintype "passive"))
      (node (ref "R19") (pin "1") (pinfunction "1_1") (pintype "passive"))
      (node (ref "T1") (pin "1") (pinfunction "G_1") (pintype "passive"))
    )
    (net (code "44") (name "Net-(T2-D)") (class "Default")
      (node (ref "EH9") (pin "1") (pinfunction "1_1") (pintype "passive"))
      (node (ref "T2") (pin "3") (pinfunction "D_3") (pintype "passive"))
    )
    (net (code "45") (name "Net-(T2-G)") (class "Default")
      (node (ref "R18") (pin "2") (pinfunction "2_2") (pintype "passive"))
      (node (ref "R20") (pin "1") (pinfunction "1_1") (pintype "passive"))
      (node (ref "T2") (pin "1") (pinfunction "G_1") (pintype "passive"))
    )
    (net (code "46") (name "Net-(U1-VO)") (class "Default")
      (node (ref "POT1") (pin "2") (pinfunction "2_2") (pintype "passive"))
      (node (ref "U1") (pin "3") (pinfunction "VO_3") (pintype "passive"))
    )
    (net (code "47") (name "Net-(U2-DC)") (class "Default")
      (node (ref "R1") (pin "2") (pinfunction "2_2") (pintype "passive"))
      (node (ref "U2") (pin "1") (pinfunction "SWC_1") (pintype "passive"))
      (node (ref "U2") (pin "7") (pinfunction "IPK_7") (pintype "passive"))
      (node (ref "U2") (pin "8") (pinfunction "DC_8") (pintype "passive"))
    )
    (net (code "48") (name "Net-(U2-FB)") (class "Default")
      (node (ref "R12") (pin "1") (pinfunction "1_1") (pintype "passive"))
      (node (ref "R8") (pin "1") (pinfunction "1_1") (pintype "passive"))
      (node (ref "U2") (pin "5") (pinfunction "FB_5") (pintype "passive"))
    )
    (net (code "49") (name "Net-(U2-TC)") (class "Default")
      (node (ref "C4") (pin "2") (pinfunction "2_2") (pintype "passive"))
      (node (ref "U2") (pin "3") (pinfunction "TC_3") (pintype "output"))
    )
    (net (code "50") (name "Net-(U3-T+)") (class "Default")
      (node (ref "EH8") (pin "2") (pinfunction "2_2") (pintype "passive"))
      (node (ref "U3") (pin "3") (pinfunction "T+_3") (pintype "passive"))
    )
    (net (code "51") (name "Net-(U3-T-)") (class "Default")
      (node (ref "EH8") (pin "1") (pinfunction "1_1") (pintype "passive"))
      (node (ref "U3") (pin "2") (pinfunction "T-_2") (pintype "passive"))
    )
    (net (code "52") (name "Net-(U4-NRST)") (class "Default")
      (node (ref "R21") (pin "2") (pinfunction "2_2") (pintype "passive"))
      (node (ref "SW4") (pin "2") (pinfunction "2_2") (pintype "passive"))
      (node (ref "U4") (pin "7") (pinfunction "NRST_7") (pintype "passive"))
    )
    (net (code "53") (name "Net-(U4-VDDA)") (class "Default")
      (node (ref "L2") (pin "2") (pinfunction "2_2") (pintype "passive"))
      (node (ref "U4") (pin "9") (pinfunction "VDDA_9") (pintype "passive"))
    )
    (net (code "54") (name "unconnected-(EH4-Pad3)") (class "Default")
      (node (ref "EH4") (pin "3") (pinfunction "3_3") (pintype "passive"))
    )
    (net (code "55") (name "unconnected-(U1-DB0-Pad7)") (class "Default")
      (node (ref "U1") (pin "7") (pinfunction "DB0_7") (pintype "bidirectional"))
    )
    (net (code "56") (name "unconnected-(U1-DB1-Pad8)") (class "Default")
      (node (ref "U1") (pin "8") (pinfunction "DB1_8") (pintype "bidirectional"))
    )
    (net (code "57") (name "unconnected-(U1-DB2-Pad9)") (class "Default")
      (node (ref "U1") (pin "9") (pinfunction "DB2_9") (pintype "bidirectional"))
    )
    (net (code "58") (name "unconnected-(U1-DB3-Pad10)") (class "Default")
      (node (ref "U1") (pin "10") (pinfunction "DB3_10") (pintype "bidirectional"))
    )
    (net (code "59") (name "unconnected-(U3-NC-Pad5)") (class "Default")
      (node (ref "U3") (pin "5") (pinfunction "NC_5") (pintype "passive+no_connect"))
    )
    (net (code "60") (name "unconnected-(U4-BOOT0-Pad44)") (class "Default")
      (node (ref "U4") (pin "44") (pinfunction "BOOT0_44") (pintype "passive"))
    )
    (net (code "61") (name "unconnected-(U4-PA11-Pad32)") (class "Default")
      (node (ref "U4") (pin "32") (pinfunction "PA11_32") (pintype "passive"))
    )
    (net (code "62") (name "unconnected-(U4-PA12-Pad33)") (class "Default")
      (node (ref "U4") (pin "33") (pinfunction "PA12_33") (pintype "passive"))
    )
    (net (code "63") (name "unconnected-(U4-PB2-Pad20)") (class "Default")
      (node (ref "U4") (pin "20") (pinfunction "PB2_20") (pintype "passive"))
    )
    (net (code "64") (name "unconnected-(U4-PB5-Pad41)") (class "Default")
      (node (ref "U4") (pin "41") (pinfunction "PB5_41") (pintype "passive"))
    )
    (net (code "65") (name "unconnected-(U4-PB6-Pad42)") (class "Default")
      (node (ref "U4") (pin "42") (pinfunction "PB6_42") (pintype "passive"))
    )
    (net (code "66") (name "unconnected-(U4-PB7-Pad43)") (class "Default")
      (node (ref "U4") (pin "43") (pinfunction "PB7_43") (pintype "passive"))
    )
    (net (code "67") (name "unconnected-(U4-PB8-Pad45)") (class "Default")
      (node (ref "U4") (pin "45") (pinfunction "PB8_45") (pintype "passive"))
    )
    (net (code "68") (name "unconnected-(U4-PB9-Pad46)") (class "Default")
      (node (ref "U4") (pin "46") (pinfunction "PB9_46") (pintype "passive"))
    )
    (net (code "69") (name "unconnected-(U4-PC13-Pad2)") (class "Default")
      (node (ref "U4") (pin "2") (pinfunction "PC13_2") (pintype "passive"))
    )
    (net (code "70") (name "unconnected-(U4-PC14-OSC32_IN-Pad3)") (class "Default")
      (node (ref "U4") (pin "3") (pinfunction "PC14-OSC32_IN_3") (pintype "passive"))
    )
    (net (code "71") (name "unconnected-(U4-PC15-OSC32_OUT-Pad4)") (class "Default")
      (node (ref "U4") (pin "4") (pinfunction "PC15-OSC32_OUT_4") (pintype "passive"))
    )
    (net (code "72") (name "unconnected-(U4-PF6-Pad35)") (class "Default")
      (node (ref "U4") (pin "35") (pinfunction "PF6_35") (pintype "passive"))
    )
    (net (code "73") (name "unconnected-(U4-PF7-Pad36)") (class "Default")
      (node (ref "U4") (pin "36") (pinfunction "PF7_36") (pintype "passive"))
    )
    (net (code "74") (name "unconnected-(U4-VSS-Pad47)") (class "Default")
      (node (ref "U4") (pin "47") (pinfunction "VSS_47") (pintype "passive"))
    )
  )
)
